# CurrentSrc.net
KiCad netlist of a schematic drawn in Altium Designer
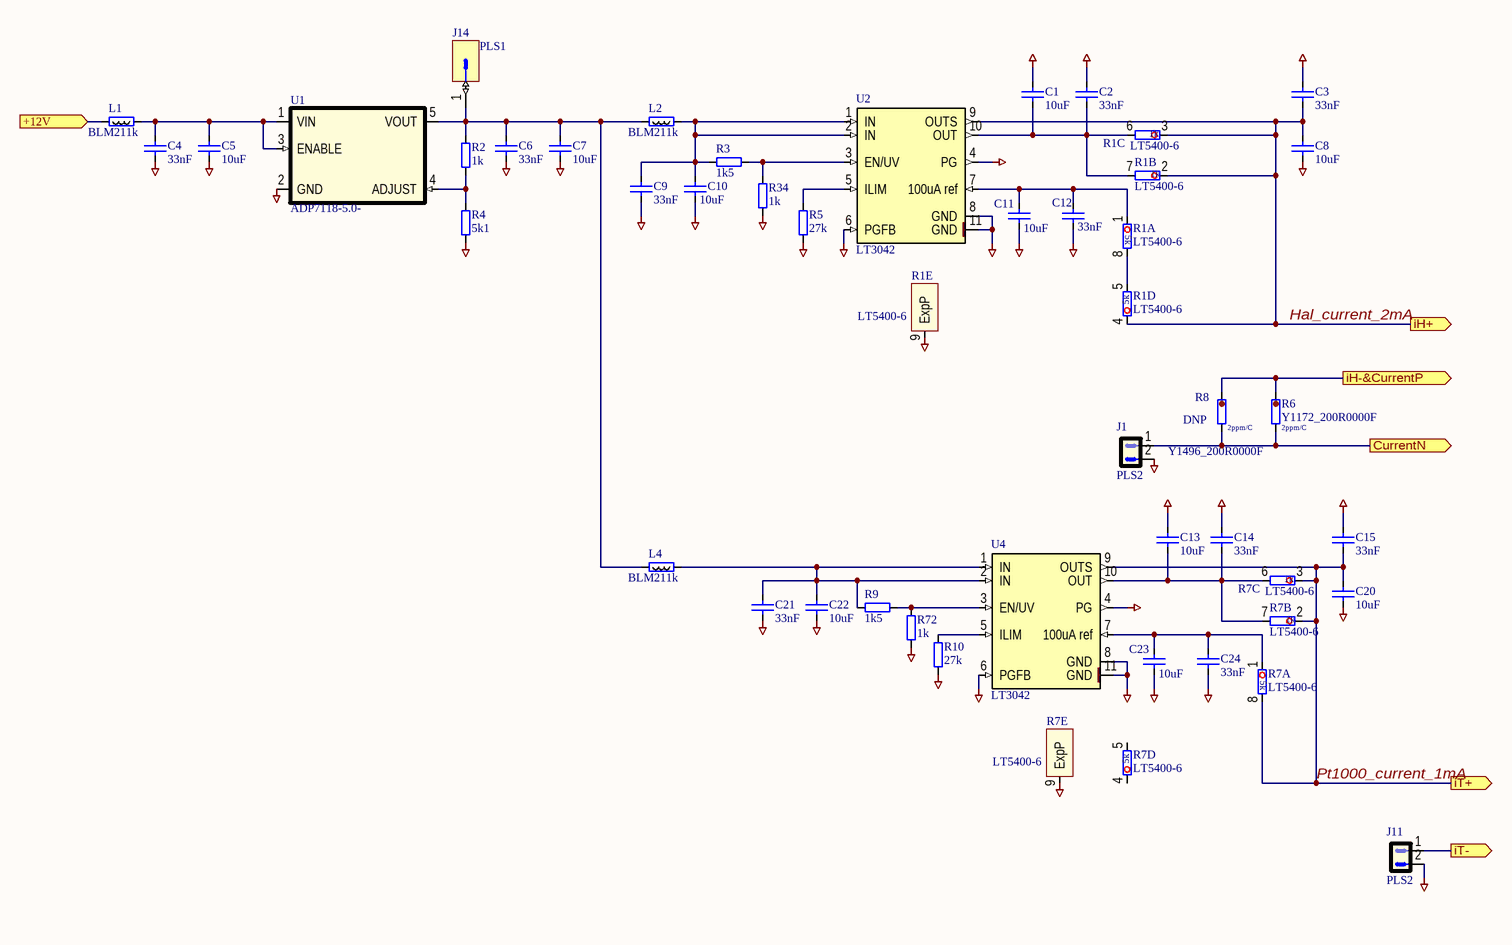
[diagram p0: CurrentSrc.SchDoc]

(export (version "E")
  (design (tool "Eeschema 10.0.6"))
  (components
    (comp (ref "C1")
      (value "10uF")
      (footprint "SMD0805CAP")
      (description "Чип конденсатор 0805")
      (fields (field (name "VOLTAGE") "25V") (field (name "TOLERANCE") "20%"))
      (libsource (lib "DDSintLib") (part "C0805"))
    )
    (comp (ref "C2")
      (value "33nF")
      (footprint "SMD0805CAP")
      (description "Чип конденсатор 0805")
      (fields (field (name "VOLTAGE") "25V") (field (name "TOLERANCE") "20%"))
      (libsource (lib "DDSintLib") (part "C0805"))
    )
    (comp (ref "C3")
      (value "33nF")
      (footprint "SMD0805CAP")
      (description "Чип конденсатор 0805")
      (fields (field (name "VOLTAGE") "25V") (field (name "TOLERANCE") "20%"))
      (libsource (lib "DDSintLib") (part "C0805"))
    )
    (comp (ref "C4")
      (value "33nF")
      (footprint "SMD0805CAP")
      (description "Чип конденсатор 0805")
      (fields (field (name "VOLTAGE") "25V") (field (name "TOLERANCE") "20%"))
      (libsource (lib "DDSintLib") (part "C0805"))
    )
    (comp (ref "C5")
      (value "10uF")
      (footprint "SMD0805CAP")
      (description "Чип конденсатор 0805")
      (fields (field (name "VOLTAGE") "25V") (field (name "TOLERANCE") "20%"))
      (libsource (lib "DDSintLib") (part "C0805"))
    )
    (comp (ref "C6")
      (value "33nF")
      (footprint "SMD0805CAP")
      (description "Чип конденсатор 0805")
      (fields (field (name "VOLTAGE") "25V") (field (name "TOLERANCE") "20%"))
      (libsource (lib "DDSintLib") (part "C0805"))
    )
    (comp (ref "C7")
      (value "10uF")
      (footprint "SMD0805CAP")
      (description "Чип конденсатор 0805")
      (fields (field (name "VOLTAGE") "25V") (field (name "TOLERANCE") "20%"))
      (libsource (lib "DDSintLib") (part "C0805"))
    )
    (comp (ref "C8")
      (value "10uF")
      (footprint "SMD0805CAP")
      (description "Чип конденсатор 0805")
      (fields (field (name "VOLTAGE") "25V") (field (name "TOLERANCE") "20%"))
      (libsource (lib "DDSintLib") (part "C0805"))
    )
    (comp (ref "C9")
      (value "33nF")
      (footprint "SMD0805CAP")
      (description "Чип конденсатор 0805")
      (fields (field (name "VOLTAGE") "25V") (field (name "TOLERANCE") "20%"))
      (libsource (lib "DDSintLib") (part "C0805"))
    )
    (comp (ref "C10")
      (value "10uF")
      (footprint "SMD0805CAP")
      (description "Чип конденсатор 0805")
      (fields (field (name "VOLTAGE") "25V") (field (name "TOLERANCE") "20%"))
      (libsource (lib "DDSintLib") (part "C0805"))
    )
    (comp (ref "C11")
      (value "10uF")
      (footprint "SMD0805CAP")
      (description "Чип конденсатор 0805")
      (fields (field (name "VOLTAGE") "25V") (field (name "TOLERANCE") "20%"))
      (libsource (lib "DDSintLib") (part "C0805"))
    )
    (comp (ref "C12")
      (value "33nF")
      (footprint "SMD0805CAP")
      (description "Чип конденсатор 0805")
      (fields (field (name "VOLTAGE") "25V") (field (name "TOLERANCE") "20%"))
      (libsource (lib "DDSintLib") (part "C0805"))
    )
    (comp (ref "C13")
      (value "10uF")
      (footprint "SMD0805CAP")
      (description "Чип конденсатор 0805")
      (fields (field (name "VOLTAGE") "25V") (field (name "TOLERANCE") "20%"))
      (libsource (lib "DDSintLib") (part "C0805"))
    )
    (comp (ref "C14")
      (value "33nF")
      (footprint "SMD0805CAP")
      (description "Чип конденсатор 0805")
      (fields (field (name "VOLTAGE") "25V") (field (name "TOLERANCE") "20%"))
      (libsource (lib "DDSintLib") (part "C0805"))
    )
    (comp (ref "C15")
      (value "33nF")
      (footprint "SMD0805CAP")
      (description "Чип конденсатор 0805")
      (fields (field (name "VOLTAGE") "25V") (field (name "TOLERANCE") "20%"))
      (libsource (lib "DDSintLib") (part "C0805"))
    )
    (comp (ref "C20")
      (value "10uF")
      (footprint "SMD0805CAP")
      (description "Чип конденсатор 0805")
      (fields (field (name "VOLTAGE") "25V") (field (name "TOLERANCE") "20%"))
      (libsource (lib "DDSintLib") (part "C0805"))
    )
    (comp (ref "C21")
      (value "33nF")
      (footprint "SMD0805CAP")
      (description "Чип конденсатор 0805")
      (fields (field (name "VOLTAGE") "25V") (field (name "TOLERANCE") "20%"))
      (libsource (lib "DDSintLib") (part "C0805"))
    )
    (comp (ref "C22")
      (value "10uF")
      (footprint "SMD0805CAP")
      (description "Чип конденсатор 0805")
      (fields (field (name "VOLTAGE") "25V") (field (name "TOLERANCE") "20%"))
      (libsource (lib "DDSintLib") (part "C0805"))
    )
    (comp (ref "C23")
      (value "10uF")
      (footprint "SMD0805CAP")
      (description "Чип конденсатор 0805")
      (fields (field (name "VOLTAGE") "25V") (field (name "TOLERANCE") "20%"))
      (libsource (lib "DDSintLib") (part "C0805"))
    )
    (comp (ref "C24")
      (value "33nF")
      (footprint "CAPC1608X87N")
      (description "Чип конденсатор 0603")
      (fields (field (name "VOLTAGE") "50V") (field (name "TOLERANCE") "20%"))
      (libsource (lib "DDSintLib") (part "C0603"))
    )
    (comp (ref "J1") (value "PLS2") (footprint "PLS2") (libsource (lib "DDSintLib") (part "PLS2")))
    (comp (ref "J11") (value "PLS2") (footprint "PLS2") (libsource (lib "DDSintLib") (part "PLS2")))
    (comp (ref "J14")
      (value "PLS1")
      (footprint "PLS1")
      (description "Штырь PLS1")
      (libsource (lib "DDSintLib") (part "PLS1"))
    )
    (comp (ref "L1")
      (value "BLM211k")
      (footprint "RESC2012X50N")
      (description "SMD Ferrite bead 0805")
      (libsource (lib "DDSintLib") (part "BLM21"))
    )
    (comp (ref "L2")
      (value "BLM211k")
      (footprint "RESC2012X50N")
      (description "SMD Ferrite bead 0805")
      (libsource (lib "DDSintLib") (part "BLM21"))
    )
    (comp (ref "L4")
      (value "BLM211k")
      (footprint "RESC2012X50N")
      (description "SMD Ferrite bead 0805")
      (libsource (lib "DDSintLib") (part "BLM21"))
    )
    (comp (ref "R1")
      (value "LT5400-6")
      (footprint "SOP65P488X110-9N-R178X241")
      (description "4 прецизионных резистора")
      (fields (field (name "TOLERANCE") "0..025%"))
      (libsource (lib "") (part "LT5400_3"))
    )
    (comp (ref "R2")
      (value "1k")
      (footprint "SMD0805RES")
      (description "Чип резистор 0805")
      (fields (field (name "TOLERANCE") "1%"))
      (libsource (lib "DDSintLib") (part "R0805"))
    )
    (comp (ref "R3")
      (value "1k5")
      (footprint "SMD0805RES")
      (description "Чип резистор 0805")
      (fields (field (name "TOLERANCE") "1%"))
      (libsource (lib "DDSintLib") (part "R0805"))
    )
    (comp (ref "R4")
      (value "5k1")
      (footprint "SMD0805RES")
      (description "Чип резистор 0805")
      (fields (field (name "TOLERANCE") "1%"))
      (libsource (lib "DDSintLib") (part "R0805"))
    )
    (comp (ref "R5")
      (value "27k")
      (footprint "SMD0805RES")
      (description "Чип резистор 0805")
      (fields (field (name "TOLERANCE") "1%"))
      (libsource (lib "DDSintLib") (part "R0805"))
    )
    (comp (ref "R6")
      (value "Y1172_200R0000F")
      (footprint "SMD0805RES")
      (description "Прецизионный чип резистор 0805")
      (fields (field (name "TOLERANCE") "1%") (field (name "TC") "2ppm/C"))
      (libsource (lib "DDS1") (part "Y1172"))
    )
    (comp (ref "R7")
      (value "LT5400-6")
      (footprint "SOP65P488X110-9N-R178X241")
      (description "4 прецизионных резистора")
      (fields (field (name "TOLERANCE") "0..025%"))
      (libsource (lib "DDSintLib") (part "LT5400"))
    )
    (comp (ref "R8")
      (value "Y1496_200R0000F")
      (footprint "RESC3016X65N")
      (description "Прецизионный чип резистор 1206")
      (fields
        (field (name "SOLDER OPTION") "DNP")
        (field (name "TC") "2ppm/C")
        (field (name "TOLERANCE") "1%")
      )
      (libsource (lib "DDSintLib") (part "Y1496"))
    )
    (comp (ref "R9")
      (value "1k5")
      (footprint "SMD0805RES")
      (description "Чип резистор 0805")
      (fields (field (name "TOLERANCE") "1%"))
      (libsource (lib "DDSintLib") (part "R0805"))
    )
    (comp (ref "R10")
      (value "27k")
      (footprint "SMD0805RES")
      (description "Чип резистор 0805")
      (fields (field (name "TOLERANCE") "1%"))
      (libsource (lib "DDSintLib") (part "R0805"))
    )
    (comp (ref "R34")
      (value "1k")
      (footprint "SMD0805RES")
      (description "Чип резистор 0805")
      (fields (field (name "TOLERANCE") "1%"))
      (libsource (lib "DDSintLib") (part "R0805"))
    )
    (comp (ref "R72")
      (value "1k")
      (footprint "SMD0805RES")
      (description "Чип резистор 0805")
      (fields (field (name "TOLERANCE") "1%"))
      (libsource (lib "DDSintLib") (part "R0805"))
    )
    (comp (ref "U1")
      (value "ADP7118-5.0-")
      (footprint "SOT23-5")
      (description "Positive LDO Linear stabilizer")
      (libsource (lib "DDSintLib") (part "ADP7118"))
    )
    (comp (ref "U2")
      (value "LT3042")
      (footprint "SOP50P490X110-11N-R157X188")
      (description "Current source v 100uA ref")
      (fields (field (name "TOLERANCE") "1%") (field (name "VOLTAGE") "max 20V"))
      (libsource (lib "DDSintLib") (part "LT3042"))
    )
    (comp (ref "U4")
      (value "LT3042")
      (footprint "SOP50P490X110-11N-R157X188")
      (description "Current source v 100uA ref")
      (fields (field (name "TOLERANCE") "1%") (field (name "VOLTAGE") "max 20V"))
      (libsource (lib "DDSintLib") (part "LT3042"))
    )
  )
  (nets
    (net (code "1") (name "/+12V") (class "Default")
      (node (ref "L1") (pin "1") (pinfunction "1_1") (pintype "passive"))
    )
    (net (code "2") (name "/CurrentN") (class "Default")
      (node (ref "J1") (pin "1") (pinfunction "1_1") (pintype "bidirectional"))
      (node (ref "R6") (pin "1") (pinfunction "1_1") (pintype "passive"))
      (node (ref "R8") (pin "1") (pinfunction "1_1") (pintype "passive"))
    )
    (net (code "3") (name "/Hal_current_2mA") (class "Default")
      (node (ref "C3") (pin "2") (pinfunction "2_2") (pintype "passive"))
      (node (ref "C8") (pin "2") (pinfunction "2_2") (pintype "passive"))
      (node (ref "R1") (pin "2") (pinfunction "2_2") (pintype "passive"))
      (node (ref "R1") (pin "3") (pinfunction "3_3") (pintype "passive"))
      (node (ref "R1") (pin "4") (pinfunction "4_4") (pintype "passive"))
      (node (ref "U2") (pin "9") (pinfunction "OUTS_9") (pintype "output"))
    )
    (net (code "4") (name "/Pt1000_current_1mA") (class "Default")
      (node (ref "C15") (pin "2") (pinfunction "2_2") (pintype "passive"))
      (node (ref "C20") (pin "2") (pinfunction "2_2") (pintype "passive"))
      (node (ref "R7") (pin "2") (pinfunction "2_2") (pintype "passive"))
      (node (ref "R7") (pin "3") (pinfunction "3_3") (pintype "passive"))
      (node (ref "R7") (pin "8") (pinfunction "8_8") (pintype "passive"))
      (node (ref "U4") (pin "9") (pinfunction "OUTS_9") (pintype "output"))
    )
    (net (code "5") (name "/iH-&CurrentP") (class "Default")
      (node (ref "R6") (pin "2") (pinfunction "2_2") (pintype "passive"))
      (node (ref "R8") (pin "2") (pinfunction "2_2") (pintype "passive"))
    )
    (net (code "6") (name "/iT-") (class "Default")
      (node (ref "J11") (pin "1") (pinfunction "1_1") (pintype "bidirectional"))
    )
    (net (code "7") (name "GND") (class "Default")
      (node (ref "C1") (pin "2") (pinfunction "2_2") (pintype "passive"))
      (node (ref "C10") (pin "1") (pinfunction "1_1") (pintype "passive"))
      (node (ref "C11") (pin "1") (pinfunction "1_1") (pintype "passive"))
      (node (ref "C12") (pin "1") (pinfunction "1_1") (pintype "passive"))
      (node (ref "C13") (pin "2") (pinfunction "2_2") (pintype "passive"))
      (node (ref "C14") (pin "2") (pinfunction "2_2") (pintype "passive"))
      (node (ref "C15") (pin "1") (pinfunction "1_1") (pintype "passive"))
      (node (ref "C2") (pin "2") (pinfunction "2_2") (pintype "passive"))
      (node (ref "C20") (pin "1") (pinfunction "1_1") (pintype "passive"))
      (node (ref "C21") (pin "1") (pinfunction "1_1") (pintype "passive"))
      (node (ref "C22") (pin "1") (pinfunction "1_1") (pintype "passive"))
      (node (ref "C23") (pin "1") (pinfunction "1_1") (pintype "passive"))
      (node (ref "C24") (pin "1") (pinfunction "1_1") (pintype "passive"))
      (node (ref "C3") (pin "1") (pinfunction "1_1") (pintype "passive"))
      (node (ref "C4") (pin "1") (pinfunction "1_1") (pintype "passive"))
      (node (ref "C5") (pin "1") (pinfunction "1_1") (pintype "passive"))
      (node (ref "C6") (pin "1") (pinfunction "1_1") (pintype "passive"))
      (node (ref "C7") (pin "1") (pinfunction "1_1") (pintype "passive"))
      (node (ref "C8") (pin "1") (pinfunction "1_1") (pintype "passive"))
      (node (ref "C9") (pin "1") (pinfunction "1_1") (pintype "passive"))
      (node (ref "J1") (pin "2") (pinfunction "2_2") (pintype "bidirectional"))
      (node (ref "J11") (pin "2") (pinfunction "2_2") (pintype "bidirectional"))
      (node (ref "R1") (pin "9") (pinfunction "ExpP_9") (pintype "passive"))
      (node (ref "R10") (pin "1") (pinfunction "1_1") (pintype "passive"))
      (node (ref "R34") (pin "1") (pinfunction "1_1") (pintype "passive"))
      (node (ref "R4") (pin "1") (pinfunction "1_1") (pintype "passive"))
      (node (ref "R5") (pin "1") (pinfunction "1_1") (pintype "passive"))
      (node (ref "R7") (pin "9") (pinfunction "ExpP_9") (pintype "passive"))
      (node (ref "R72") (pin "1") (pinfunction "1_1") (pintype "passive"))
      (node (ref "U1") (pin "2") (pinfunction "GND_2") (pintype "power_in"))
      (node (ref "U2") (pin "11") (pinfunction "GND_11") (pintype "power_in"))
      (node (ref "U2") (pin "4") (pinfunction "PG_4") (pintype "output"))
      (node (ref "U2") (pin "6") (pinfunction "PGFB_6") (pintype "input"))
      (node (ref "U2") (pin "8") (pinfunction "GND_8") (pintype "power_in"))
      (node (ref "U4") (pin "11") (pinfunction "GND_11") (pintype "power_in"))
      (node (ref "U4") (pin "4") (pinfunction "PG_4") (pintype "output"))
      (node (ref "U4") (pin "6") (pinfunction "PGFB_6") (pintype "input"))
      (node (ref "U4") (pin "8") (pinfunction "GND_8") (pintype "power_in"))
    )
    (net (code "8") (name "Net-(C10-Pad2)") (class "Default")
      (node (ref "C10") (pin "2") (pinfunction "2_2") (pintype "passive"))
      (node (ref "C9") (pin "2") (pinfunction "2_2") (pintype "passive"))
      (node (ref "L2") (pin "2") (pinfunction "2_2") (pintype "passive"))
      (node (ref "R3") (pin "1") (pinfunction "1_1") (pintype "passive"))
      (node (ref "U2") (pin "1") (pinfunction "IN_1") (pintype "input"))
      (node (ref "U2") (pin "2") (pinfunction "IN_2") (pintype "input"))
    )
    (net (code "9") (name "Net-(C21-Pad2)") (class "Default")
      (node (ref "C21") (pin "2") (pinfunction "2_2") (pintype "passive"))
      (node (ref "C22") (pin "2") (pinfunction "2_2") (pintype "passive"))
      (node (ref "L4") (pin "2") (pinfunction "2_2") (pintype "passive"))
      (node (ref "R9") (pin "1") (pinfunction "1_1") (pintype "passive"))
      (node (ref "U4") (pin "1") (pinfunction "IN_1") (pintype "input"))
      (node (ref "U4") (pin "2") (pinfunction "IN_2") (pintype "input"))
    )
    (net (code "10") (name "Net-(R1-Pad5)") (class "Default")
      (node (ref "R1") (pin "5") (pinfunction "5_5") (pintype "passive"))
      (node (ref "R1") (pin "8") (pinfunction "8_8") (pintype "passive"))
    )
    (net (code "11") (name "Net-(U1-ADJUST)") (class "Default")
      (node (ref "R2") (pin "1") (pinfunction "1_1") (pintype "passive"))
      (node (ref "R4") (pin "2") (pinfunction "2_2") (pintype "passive"))
      (node (ref "U1") (pin "4") (pinfunction "ADJUST_4") (pintype "input"))
    )
    (net (code "12") (name "Net-(U1-ENABLE)") (class "Default")
      (node (ref "C4") (pin "2") (pinfunction "2_2") (pintype "passive"))
      (node (ref "C5") (pin "2") (pinfunction "2_2") (pintype "passive"))
      (node (ref "L1") (pin "2") (pinfunction "2_2") (pintype "passive"))
      (node (ref "U1") (pin "1") (pinfunction "VIN_1") (pintype "power_in"))
      (node (ref "U1") (pin "3") (pinfunction "ENABLE_3") (pintype "input"))
    )
    (net (code "13") (name "Net-(U1-VOUT)") (class "Default")
      (node (ref "C6") (pin "2") (pinfunction "2_2") (pintype "passive"))
      (node (ref "C7") (pin "2") (pinfunction "2_2") (pintype "passive"))
      (node (ref "J14") (pin "1") (pinfunction "1_1") (pintype "bidirectional"))
      (node (ref "L2") (pin "1") (pinfunction "1_1") (pintype "passive"))
      (node (ref "L4") (pin "1") (pinfunction "1_1") (pintype "passive"))
      (node (ref "R2") (pin "2") (pinfunction "2_2") (pintype "passive"))
      (node (ref "U1") (pin "5") (pinfunction "VOUT_5") (pintype "power_in"))
    )
    (net (code "14") (name "Net-(U2-100uA_ref)") (class "Default")
      (node (ref "C11") (pin "2") (pinfunction "2_2") (pintype "passive"))
      (node (ref "C12") (pin "2") (pinfunction "2_2") (pintype "passive"))
      (node (ref "R1") (pin "1") (pinfunction "1_1") (pintype "passive"))
      (node (ref "U2") (pin "7") (pinfunction "100uA_ref_7") (pintype "input"))
    )
    (net (code "15") (name "Net-(U2-EN{slash}UV)") (class "Default")
      (node (ref "R3") (pin "2") (pinfunction "2_2") (pintype "passive"))
      (node (ref "R34") (pin "2") (pinfunction "2_2") (pintype "passive"))
      (node (ref "U2") (pin "3") (pinfunction "EN/UV_3") (pintype "input"))
    )
    (net (code "16") (name "Net-(U2-ILIM)") (class "Default")
      (node (ref "R5") (pin "2") (pinfunction "2_2") (pintype "passive"))
      (node (ref "U2") (pin "5") (pinfunction "ILIM_5") (pintype "input"))
    )
    (net (code "17") (name "Net-(U2-OUT)") (class "Default")
      (node (ref "C1") (pin "1") (pinfunction "1_1") (pintype "passive"))
      (node (ref "C2") (pin "1") (pinfunction "1_1") (pintype "passive"))
      (node (ref "R1") (pin "6") (pinfunction "6_6") (pintype "passive"))
      (node (ref "R1") (pin "7") (pinfunction "7_7") (pintype "passive"))
      (node (ref "U2") (pin "10") (pinfunction "OUT_10") (pintype "output"))
    )
    (net (code "18") (name "Net-(U4-100uA_ref)") (class "Default")
      (node (ref "C23") (pin "2") (pinfunction "2_2") (pintype "passive"))
      (node (ref "C24") (pin "2") (pinfunction "2_2") (pintype "passive"))
      (node (ref "R7") (pin "1") (pinfunction "1_1") (pintype "passive"))
      (node (ref "U4") (pin "7") (pinfunction "100uA_ref_7") (pintype "input"))
    )
    (net (code "19") (name "Net-(U4-EN{slash}UV)") (class "Default")
      (node (ref "R72") (pin "2") (pinfunction "2_2") (pintype "passive"))
      (node (ref "R9") (pin "2") (pinfunction "2_2") (pintype "passive"))
      (node (ref "U4") (pin "3") (pinfunction "EN/UV_3") (pintype "input"))
    )
    (net (code "20") (name "Net-(U4-ILIM)") (class "Default")
      (node (ref "R10") (pin "2") (pinfunction "2_2") (pintype "passive"))
      (node (ref "U4") (pin "5") (pinfunction "ILIM_5") (pintype "input"))
    )
    (net (code "21") (name "Net-(U4-OUT)") (class "Default")
      (node (ref "C13") (pin "1") (pinfunction "1_1") (pintype "passive"))
      (node (ref "C14") (pin "1") (pinfunction "1_1") (pintype "passive"))
      (node (ref "R7") (pin "6") (pinfunction "6_6") (pintype "passive"))
      (node (ref "R7") (pin "7") (pinfunction "7_7") (pintype "passive"))
      (node (ref "U4") (pin "10") (pinfunction "OUT_10") (pintype "output"))
    )
    (net (code "22") (name "unconnected-(R7-Pad4)") (class "Default")
      (node (ref "R7") (pin "4") (pinfunction "4_4") (pintype "passive"))
    )
    (net (code "23") (name "unconnected-(R7-Pad5)") (class "Default")
      (node (ref "R7") (pin "5") (pinfunction "5_5") (pintype "passive"))
    )
  )
)
